# CC3351.net
KiCad netlist of a schematic drawn in Altium Designer
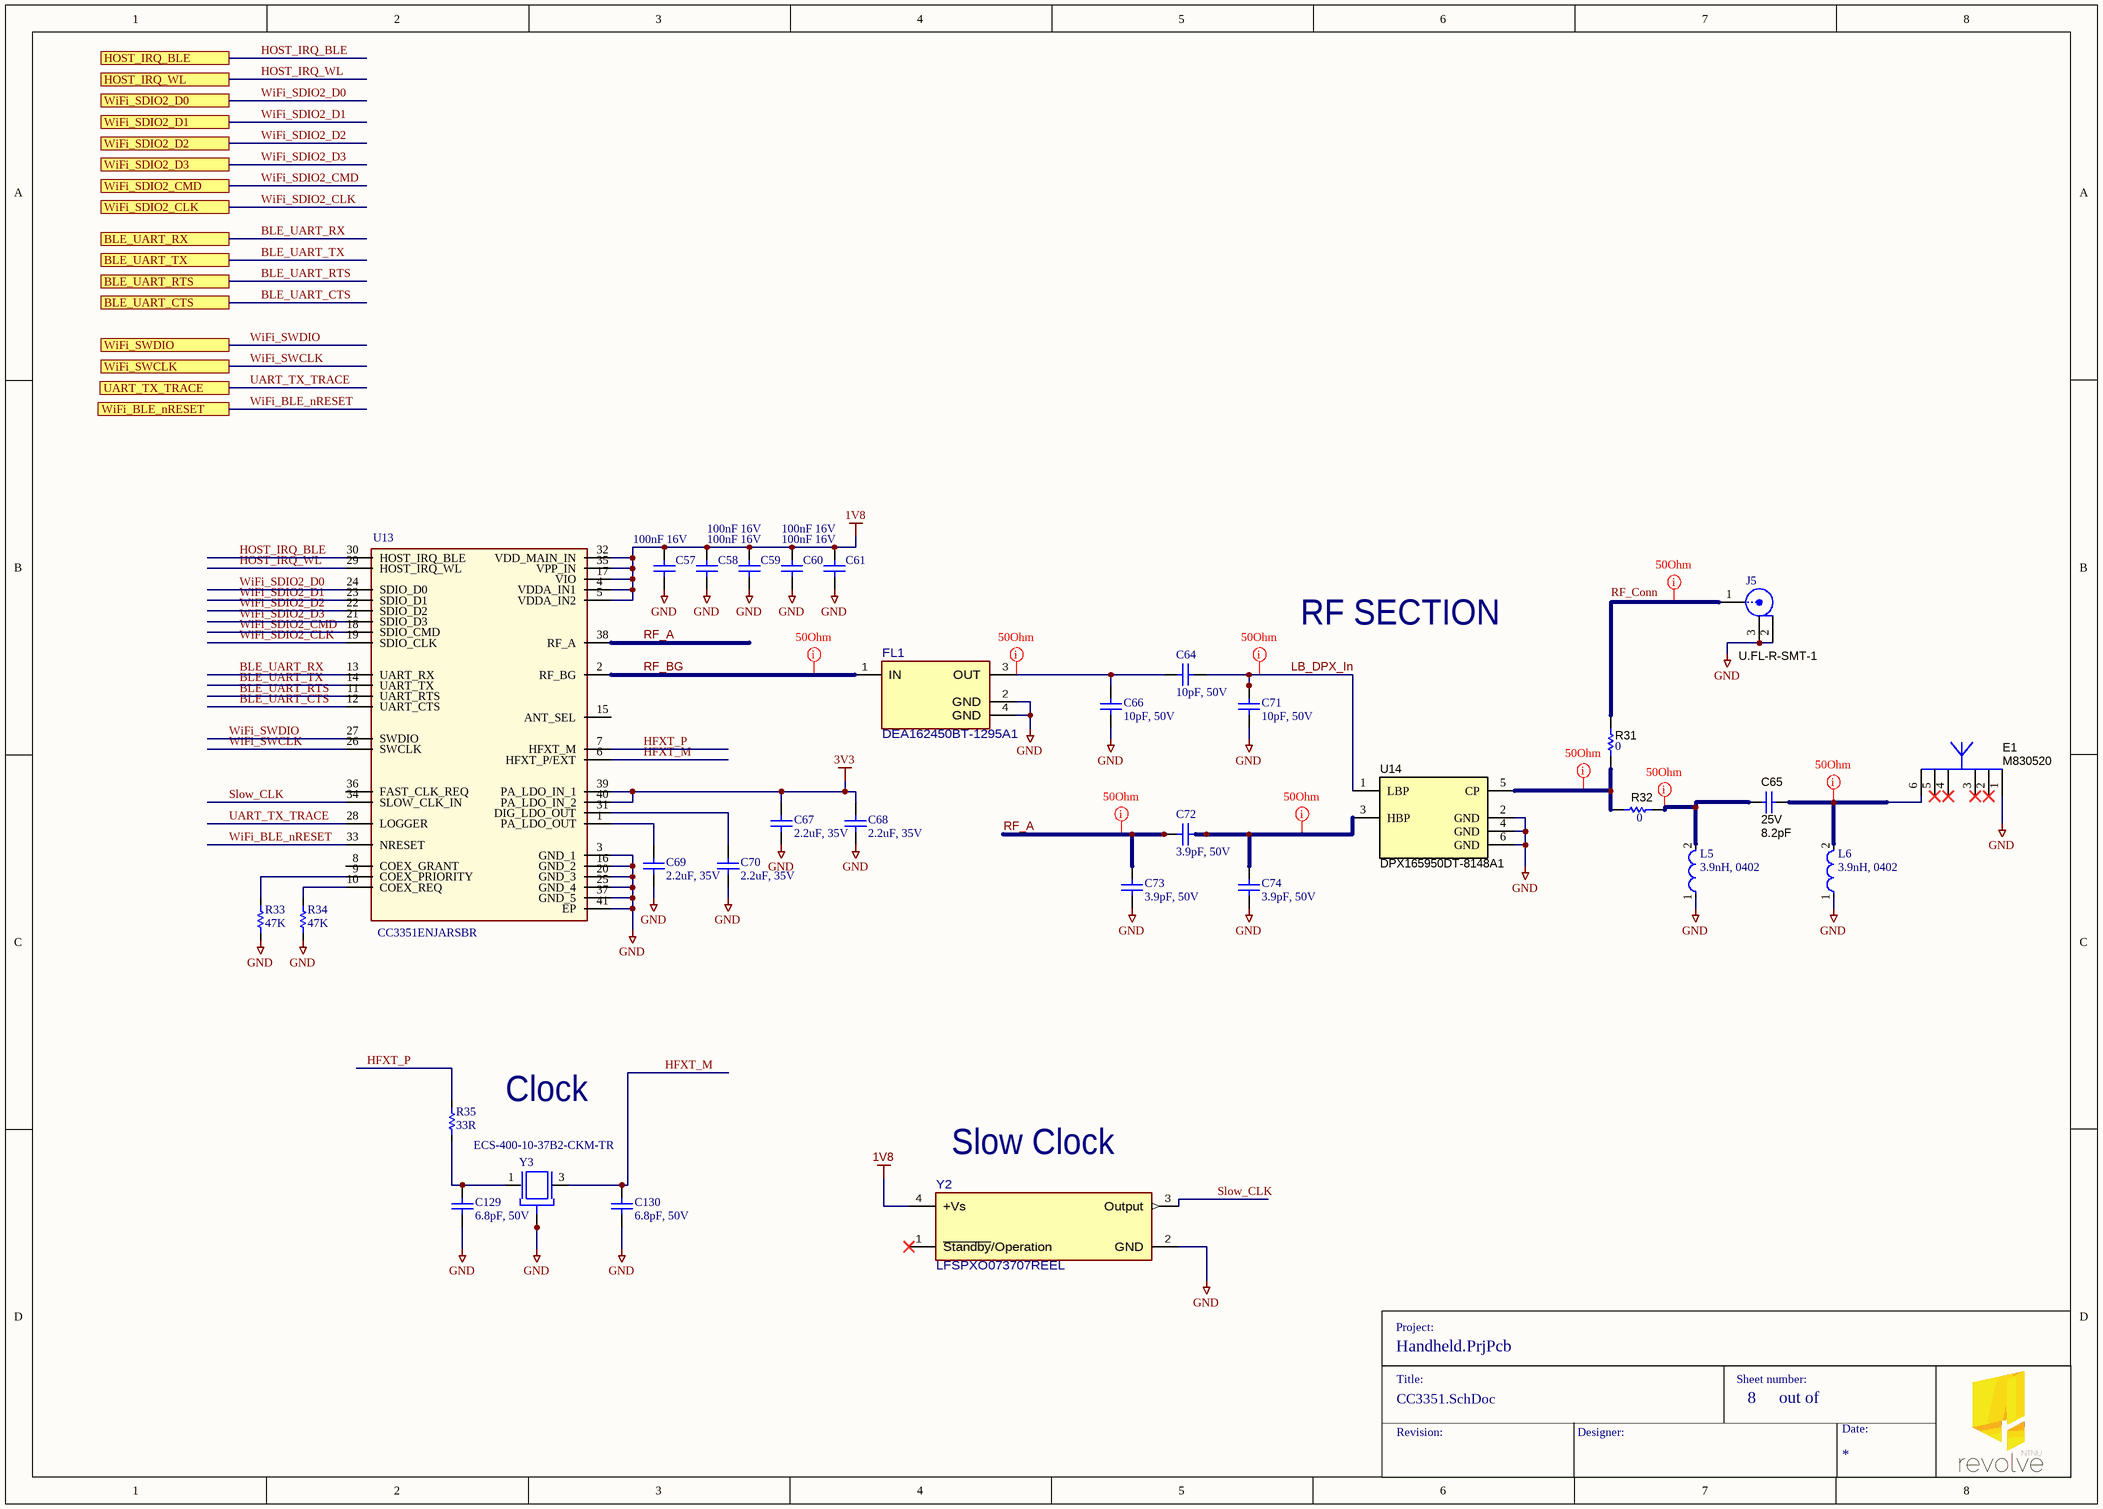
[diagram p0: CC3351.SchDoc]

(export (version "E")
  (design (tool "Eeschema 10.0.6"))
  (components
    (comp (ref "C57") (value "100nF 16V") (footprint "0402") (libsource (lib "Revolve NTNU") (part "CAP")))
    (comp (ref "C58") (value "100nF 16V") (footprint "0402") (libsource (lib "Revolve NTNU") (part "CAP")))
    (comp (ref "C59") (value "100nF 16V") (footprint "0402") (libsource (lib "Revolve NTNU") (part "CAP")))
    (comp (ref "C60") (value "100nF 16V") (footprint "0402") (libsource (lib "Revolve NTNU") (part "CAP")))
    (comp (ref "C61") (value "100nF 16V") (footprint "0402") (libsource (lib "Revolve NTNU") (part "CAP")))
    (comp (ref "C64")
      (value "10pF, 50V")
      (footprint "0402 resistor")
      (description "10pF, 50V, 10%, 0402")
      (libsource (lib "Revolve NTNU") (part "CAP"))
    )
    (comp (ref "C65")
      (value "GJM0335C1E100JB01D")
      (footprint "0201")
      (description "CAP, CERM, 8.2 pF, 25 V,+/- 1.2%, C0G/NP0, 0201")
      (fields
        (field (name "MANUFACTURER") "MuRata")
        (field (name "PARTNUMBER") "GRM0335C1E8R2BA01D")
        (field (name "VDC_V") "25V")
        (field (name "VALUEDISPLAYED") "8.2pF")
        (field (name "PUBLISHER") "Texas Instruments")
      )
      (libsource (lib "MCU127_M2-CC3351_RevA") (part "Capacitor"))
    )
    (comp (ref "C66")
      (value "10pF, 50V")
      (footprint "0402 resistor")
      (description "10pF, 50V, 10%, 0402")
      (libsource (lib "Revolve NTNU") (part "CAP"))
    )
    (comp (ref "C67")
      (value "2.2uF, 35V")
      (footprint "0402 resistor")
      (description "2.2uF, 35V, 10%, 0402")
      (libsource (lib "Revolve NTNU") (part "CAP"))
    )
    (comp (ref "C68")
      (value "2.2uF, 35V")
      (footprint "0402 resistor")
      (description "2.2uF, 35V, 10%, 0402")
      (libsource (lib "Revolve NTNU") (part "CAP"))
    )
    (comp (ref "C69")
      (value "2.2uF, 35V")
      (footprint "0402 resistor")
      (description "2.2uF, 35V, 10%, 0402")
      (libsource (lib "Revolve NTNU") (part "CAP"))
    )
    (comp (ref "C70")
      (value "2.2uF, 35V")
      (footprint "0402 resistor")
      (description "2.2uF, 35V, 10%, 0402")
      (libsource (lib "Revolve NTNU") (part "CAP"))
    )
    (comp (ref "C71")
      (value "10pF, 50V")
      (footprint "0402 resistor")
      (description "10pF, 50V, 10%, 0402")
      (libsource (lib "Revolve NTNU") (part "CAP"))
    )
    (comp (ref "C72")
      (value "3.9pF, 50V")
      (footprint "0402 resistor")
      (description "3.9pF, 50V, 10%, 0402")
      (libsource (lib "Revolve NTNU") (part "CAP"))
    )
    (comp (ref "C73")
      (value "3.9pF, 50V")
      (footprint "0402 resistor")
      (description "3.9pF, 50V, 10%, 0402")
      (libsource (lib "Revolve NTNU") (part "CAP"))
    )
    (comp (ref "C74")
      (value "3.9pF, 50V")
      (footprint "0402 resistor")
      (description "3.9pF, 50V, 10%, 0402")
      (libsource (lib "Revolve NTNU") (part "CAP"))
    )
    (comp (ref "C129")
      (value "6.8pF, 50V")
      (footprint "0402 resistor")
      (description "6.8pF, 50V, 10%, 0402")
      (libsource (lib "Revolve NTNU") (part "CAP"))
    )
    (comp (ref "C130")
      (value "6.8pF, 50V")
      (footprint "0402 resistor")
      (description "6.8pF, 50V, 10%, 0402")
      (libsource (lib "Revolve NTNU") (part "CAP"))
    )
    (comp (ref "E1")
      (value "M830520")
      (footprint "Ethertronics_M830520")
      (description "WLAN ANTENNA 802.11, SMD")
      (fields
        (field (name "MANUFACTURER") "Ethertronics")
        (field (name "ALTERNATE PARTNUMBER") "----")
        (field (name "PUBLISHER") "Texas Instruments")
      )
      (libsource (lib "MCU127_M2-CC3351_RevA") (part "CMP-0001857-1"))
    )
    (comp (ref "FL1")
      (value "DEA162450BT-1295A1")
      (footprint "FP-DEA162450BT-1295A1_SMT_FILTER_1MM60_0MM80-MFG")
      (fields
        (field (name "MOUSER PART NUMBER") "810-DEA162450BT1295A")
        (field (name "MANUFACTURER") "TDK")
        (field (name "DIGIKEY PART NUMBER") "445-175610-1-ND")
      )
      (libsource (lib "MCU127_M2-CC3351_RevA") (part "SYM-DEA162450BT-1295A1"))
    )
    (comp (ref "J5")
      (value "U.FL-R-SMT-1")
      (footprint "CONN_UFL-R-SMT-1")
      (description "Receptacle, Ultra Miniature Coaxial, Male Pin, 50 ohm, SMT")
      (fields
        (field (name "MANUFACTURER") "Hirose Electric Co. Ltd.")
        (field (name "PARTNUMBER") "U.FL-R-SMT-1(01)")
        (field (name "PUBLISHER") "Texas Instruments")
      )
      (libsource (lib "MCU127_M2-CC3351_RevA") (part "SMA_Contact1_GND23"))
    )
    (comp (ref "L5")
      (value "3.9nH, 0402")
      (footprint "INDC1005X55N")
      (description "3.9 nH Unshielded Multilayer Inductor 750 mA 140mOhm Max 0402 (1005 Metric)")
      (fields (field (name "TOLERANCE") "30%"))
      (libsource (lib "Handheld") (part "Inductor SMD 3.9nH"))
    )
    (comp (ref "L6")
      (value "3.9nH, 0402")
      (footprint "INDC1005X55N")
      (description "3.9 nH Unshielded Multilayer Inductor 750 mA 140mOhm Max 0402 (1005 Metric)")
      (fields (field (name "TOLERANCE") "30%"))
      (libsource (lib "Handheld") (part "Inductor SMD 3.9nH"))
    )
    (comp (ref "R31")
      (value "CRCW02010000Z0ED")
      (footprint "0201")
      (description "RES, 0, 5%, 0.05 W, 0201")
      (fields (field (name "MANUFACTURER") "Vishay-Dale") (field (name "VALUEDISPLAYED") "0"))
      (libsource (lib "MCU127_M2-CC3351_RevA") (part "Resistor"))
    )
    (comp (ref "R32")
      (value "CRCW02010000Z0ED")
      (footprint "0201")
      (description "RES, 0, 5%, 0.05 W, 0201")
      (fields (field (name "MANUFACTURER") "Vishay-Dale") (field (name "VALUEDISPLAYED") "0"))
      (libsource (lib "MCU127_M2-CC3351_RevA") (part "Resistor"))
    )
    (comp (ref "R33")
      (value "47K")
      (footprint "0603 Resistor")
      (description "47K, 1%, 1/10W, 0603")
      (libsource (lib "Revolve NTNU") (part "Resistor"))
    )
    (comp (ref "R34")
      (value "47K")
      (footprint "0603 Resistor")
      (description "47K, 1%, 1/10W, 0603")
      (libsource (lib "Revolve NTNU") (part "Resistor"))
    )
    (comp (ref "R35")
      (value "33R")
      (footprint "0603 Resistor")
      (description "33R, 1%, 1/10W, 0603")
      (fields (field (name "TOLERANCE") "1%") (field (name "MANUFACTURER") "Panasonic"))
      (libsource (lib "Revolve NTNU") (part "Resistor"))
    )
    (comp (ref "U13")
      (value "CC3351ENJARSBR")
      (footprint "RSB0040B-MFG")
      (fields (field (name "MOUSER PART NUMBER") "595-CC3351ENJARSBR"))
      (libsource (lib "Handheld") (part "CC3351ENJARSBR"))
    )
    (comp (ref "U14")
      (value "CMP-0002040-1")
      (footprint "TDK_DPX165950DT-8148A1")
      (description "Multilayer Diplexer for 2.4GHz W-LAN & Bluetooth / 5GHz W-LAN")
      (fields
        (field (name "PARTNUMBER") "DPX165950DT-8148A1")
        (field (name "MANUFACTURER") "TDK")
        (field (name "ALTERNATE PARTNUMBER") "----")
        (field (name "PUBLISHER") "Texas Instruments")
      )
      (libsource (lib "MCU127_M2-CC3351_RevA") (part "CMP-0002040-1"))
    )
    (comp (ref "Y2")
      (value "LFSPXO073707REEL")
      (footprint "FP-LFSPXO073707REEL_SMT4_2MM0_1MM6-MFG")
      (description "32.768 kHz XO (Standard) CMOS Oscillator 1.8V Enable/Disable 4-SMD, No Lead")
      (fields
        (field (name "MANUFACTURER") "IQD Frequency Products")
        (field (name "DIGIKEY PART NUMBER") "1923-1619-1-ND")
      )
      (libsource (lib "MCU127_M2-CC3351_RevA") (part "SYM-LFSPXO073707REEL"))
    )
    (comp (ref "Y3")
      (value "ECS-400-10-37B2-CKM-TR")
      (footprint "XTAL_ECS-400-10-37B2-CKM-TR")
      (description "Crystal 40MHz ±10ppm (Tol) ±10ppm (Stability) 10pF FUND 40Ohm 4-Pin Mini-CSMD T/R")
      (fields (field (name "MF") "ECS Inc."))
      (libsource (lib "Handheld") (part "ECS-400-10-37B2-CKM-TR"))
    )
  )
  (nets
    (net (code "1") (name "/BLE_UART_CTS") (class "Default")
      (node (ref "U13") (pin "12") (pinfunction "UART_CTS_12") (pintype "passive"))
    )
    (net (code "2") (name "/BLE_UART_RTS") (class "Default")
      (node (ref "U13") (pin "11") (pinfunction "UART_RTS_11") (pintype "passive"))
    )
    (net (code "3") (name "/BLE_UART_RX") (class "Default")
      (node (ref "U13") (pin "13") (pinfunction "UART_RX_13") (pintype "passive"))
    )
    (net (code "4") (name "/BLE_UART_TX") (class "Default")
      (node (ref "U13") (pin "14") (pinfunction "UART_TX_14") (pintype "passive"))
    )
    (net (code "5") (name "/HFXT_M") (class "Default")
      (node (ref "C130") (pin "2") (pinfunction "2_2") (pintype "passive"))
      (node (ref "U13") (pin "6") (pinfunction "HFXT_P/EXT_6") (pintype "passive"))
      (node (ref "Y3") (pin "3") (pinfunction "OUT/IN_3") (pintype "passive"))
    )
    (net (code "6") (name "/HFXT_P") (class "Default")
      (node (ref "R35") (pin "2") (pinfunction "2_2") (pintype "passive"))
      (node (ref "U13") (pin "7") (pinfunction "HFXT_M_7") (pintype "passive"))
    )
    (net (code "7") (name "/HOST_IRQ_BLE") (class "Default")
      (node (ref "U13") (pin "30") (pinfunction "HOST_IRQ_BLE_30") (pintype "passive"))
    )
    (net (code "8") (name "/HOST_IRQ_WL") (class "Default")
      (node (ref "U13") (pin "29") (pinfunction "HOST_IRQ_WL_29") (pintype "passive"))
    )
    (net (code "9") (name "/LB_DPX_In") (class "Default")
      (node (ref "C64") (pin "2") (pinfunction "2_2") (pintype "passive"))
      (node (ref "C71") (pin "2") (pinfunction "2_2") (pintype "passive"))
      (node (ref "U14") (pin "1") (pinfunction "LBP_1") (pintype "passive"))
    )
    (net (code "10") (name "/RF_A") (class "Default")
      (node (ref "C72") (pin "2") (pinfunction "2_2") (pintype "passive"))
      (node (ref "C73") (pin "2") (pinfunction "2_2") (pintype "passive"))
      (node (ref "U13") (pin "38") (pinfunction "RF_A_38") (pintype "passive"))
    )
    (net (code "11") (name "/RF_BG") (class "Default")
      (node (ref "FL1") (pin "1") (pinfunction "IN_1") (pintype "passive"))
      (node (ref "U13") (pin "2") (pinfunction "RF_BG_2") (pintype "passive"))
    )
    (net (code "13") (name "/Slow_CLK") (class "Default")
      (node (ref "U13") (pin "34") (pinfunction "SLOW_CLK_IN_34") (pintype "passive"))
      (node (ref "Y2") (pin "3") (pinfunction "Output_3") (pintype "output"))
    )
    (net (code "14") (name "/UART_TX_TRACE") (class "Default")
      (node (ref "U13") (pin "28") (pinfunction "LOGGER_28") (pintype "passive"))
    )
    (net (code "15") (name "/WiFi_BLE_nRESET") (class "Default")
      (node (ref "U13") (pin "33") (pinfunction "NRESET_33") (pintype "passive"))
    )
    (net (code "16") (name "/WiFi_SDIO2_CLK") (class "Default")
      (node (ref "U13") (pin "19") (pinfunction "SDIO_CLK_19") (pintype "passive"))
    )
    (net (code "17") (name "/WiFi_SDIO2_CMD") (class "Default")
      (node (ref "U13") (pin "18") (pinfunction "SDIO_CMD_18") (pintype "passive"))
    )
    (net (code "18") (name "/WiFi_SDIO2_D0") (class "Default")
      (node (ref "U13") (pin "24") (pinfunction "SDIO_D0_24") (pintype "passive"))
    )
    (net (code "19") (name "/WiFi_SDIO2_D1") (class "Default")
      (node (ref "U13") (pin "23") (pinfunction "SDIO_D1_23") (pintype "passive"))
    )
    (net (code "20") (name "/WiFi_SDIO2_D2") (class "Default")
      (node (ref "U13") (pin "22") (pinfunction "SDIO_D2_22") (pintype "passive"))
    )
    (net (code "21") (name "/WiFi_SDIO2_D3") (class "Default")
      (node (ref "U13") (pin "21") (pinfunction "SDIO_D3_21") (pintype "passive"))
    )
    (net (code "22") (name "/WiFi_SWCLK") (class "Default")
      (node (ref "U13") (pin "26") (pinfunction "SWCLK_26") (pintype "passive"))
    )
    (net (code "23") (name "/WiFi_SWDIO") (class "Default")
      (node (ref "U13") (pin "27") (pinfunction "SWDIO_27") (pintype "passive"))
    )
    (net (code "24") (name "1V8") (class "Default")
      (node (ref "C57") (pin "2") (pinfunction "2_2") (pintype "passive"))
      (node (ref "C58") (pin "2") (pinfunction "2_2") (pintype "passive"))
      (node (ref "C59") (pin "2") (pinfunction "2_2") (pintype "passive"))
      (node (ref "C60") (pin "2") (pinfunction "2_2") (pintype "passive"))
      (node (ref "C61") (pin "2") (pinfunction "2_2") (pintype "passive"))
      (node (ref "U13") (pin "17") (pinfunction "VIO_17") (pintype "passive"))
      (node (ref "U13") (pin "32") (pinfunction "VDD_MAIN_IN_32") (pintype "passive"))
      (node (ref "U13") (pin "35") (pinfunction "VPP_IN_35") (pintype "passive"))
      (node (ref "U13") (pin "4") (pinfunction "VDDA_IN1_4") (pintype "passive"))
      (node (ref "U13") (pin "5") (pinfunction "VDDA_IN2_5") (pintype "passive"))
      (node (ref "Y2") (pin "4") (pinfunction "+Vs_4") (pintype "power_in"))
    )
    (net (code "25") (name "3V3") (class "Default")
      (node (ref "C67") (pin "2") (pinfunction "2_2") (pintype "passive"))
      (node (ref "C68") (pin "2") (pinfunction "2_2") (pintype "passive"))
      (node (ref "U13") (pin "39") (pinfunction "PA_LDO_IN_1_39") (pintype "passive"))
      (node (ref "U13") (pin "40") (pinfunction "PA_LDO_IN_2_40") (pintype "passive"))
    )
    (net (code "26") (name "GND") (class "Default")
      (node (ref "C129") (pin "1") (pinfunction "1_1") (pintype "passive"))
      (node (ref "C130") (pin "1") (pinfunction "1_1") (pintype "passive"))
      (node (ref "C57") (pin "1") (pinfunction "1_1") (pintype "passive"))
      (node (ref "C58") (pin "1") (pinfunction "1_1") (pintype "passive"))
      (node (ref "C59") (pin "1") (pinfunction "1_1") (pintype "passive"))
      (node (ref "C60") (pin "1") (pinfunction "1_1") (pintype "passive"))
      (node (ref "C61") (pin "1") (pinfunction "1_1") (pintype "passive"))
      (node (ref "C66") (pin "1") (pinfunction "1_1") (pintype "passive"))
      (node (ref "C67") (pin "1") (pinfunction "1_1") (pintype "passive"))
      (node (ref "C68") (pin "1") (pinfunction "1_1") (pintype "passive"))
      (node (ref "C69") (pin "1") (pinfunction "1_1") (pintype "passive"))
      (node (ref "C70") (pin "1") (pinfunction "1_1") (pintype "passive"))
      (node (ref "C71") (pin "1") (pinfunction "1_1") (pintype "passive"))
      (node (ref "C73") (pin "1") (pinfunction "1_1") (pintype "passive"))
      (node (ref "C74") (pin "1") (pinfunction "1_1") (pintype "passive"))
      (node (ref "E1") (pin "1") (pinfunction "Feed_1") (pintype "passive"))
      (node (ref "FL1") (pin "2") (pinfunction "GND_2") (pintype "power_in"))
      (node (ref "FL1") (pin "4") (pinfunction "GND_4") (pintype "power_in"))
      (node (ref "J5") (pin "2") (pinfunction "2_2") (pintype "passive"))
      (node (ref "J5") (pin "3") (pinfunction "3_3") (pintype "passive"))
      (node (ref "L5") (pin "1") (pinfunction "1_1") (pintype "passive"))
      (node (ref "L6") (pin "1") (pinfunction "1_1") (pintype "passive"))
      (node (ref "R33") (pin "2") (pinfunction "2_2") (pintype "passive"))
      (node (ref "R34") (pin "2") (pinfunction "2_2") (pintype "passive"))
      (node (ref "U13") (pin "16") (pinfunction "GND_2_16") (pintype "passive"))
      (node (ref "U13") (pin "20") (pinfunction "GND_3_20") (pintype "passive"))
      (node (ref "U13") (pin "25") (pinfunction "GND_4_25") (pintype "passive"))
      (node (ref "U13") (pin "3") (pinfunction "GND_1_3") (pintype "passive"))
      (node (ref "U13") (pin "37") (pinfunction "GND_5_37") (pintype "passive"))
      (node (ref "U13") (pin "41") (pinfunction "EP_41") (pintype "passive"))
      (node (ref "U14") (pin "2") (pinfunction "GND_2") (pintype "power_in"))
      (node (ref "U14") (pin "4") (pinfunction "GND_4") (pintype "power_in"))
      (node (ref "U14") (pin "6") (pinfunction "GND_6") (pintype "power_in"))
      (node (ref "Y2") (pin "2") (pinfunction "GND_2") (pintype "power_in"))
      (node (ref "Y3") (pin "2") (pinfunction "GND_2") (pintype "power_in"))
      (node (ref "Y3") (pin "4") (pinfunction "GND_4") (pintype "power_in"))
    )
    (net (code "27") (name "Net-(C65-Pad1)") (class "Default")
      (node (ref "C65") (pin "1") (pinfunction "1_1") (pintype "passive"))
      (node (ref "E1") (pin "6") (pinfunction "6_6") (pintype "passive"))
      (node (ref "L6") (pin "2") (pinfunction "2_2") (pintype "passive"))
    )
    (net (code "28") (name "Net-(C65-Pad2)") (class "Default")
      (node (ref "C65") (pin "2") (pinfunction "2_2") (pintype "passive"))
      (node (ref "L5") (pin "2") (pinfunction "2_2") (pintype "passive"))
      (node (ref "R32") (pin "2") (pinfunction "2_2") (pintype "passive"))
    )
    (net (code "29") (name "Net-(FL1-OUT)") (class "Default")
      (node (ref "C64") (pin "1") (pinfunction "1_1") (pintype "passive"))
      (node (ref "C66") (pin "2") (pinfunction "2_2") (pintype "passive"))
      (node (ref "FL1") (pin "3") (pinfunction "OUT_3") (pintype "passive"))
    )
    (net (code "30") (name "Net-(J5-Pad1)") (class "Default")
      (node (ref "J5") (pin "1") (pinfunction "1_1") (pintype "passive"))
      (node (ref "R31") (pin "2") (pinfunction "2_2") (pintype "passive"))
    )
    (net (code "31") (name "Net-(U13-COEX_PRIORITY)") (class "Default")
      (node (ref "R33") (pin "1") (pinfunction "1_1") (pintype "passive"))
      (node (ref "U13") (pin "9") (pinfunction "COEX_PRIORITY_9") (pintype "passive"))
    )
    (net (code "32") (name "Net-(U13-COEX_REQ)") (class "Default")
      (node (ref "R34") (pin "1") (pinfunction "1_1") (pintype "passive"))
      (node (ref "U13") (pin "10") (pinfunction "COEX_REQ_10") (pintype "passive"))
    )
    (net (code "33") (name "Net-(U13-DIG_LDO_OUT)") (class "Default")
      (node (ref "C70") (pin "2") (pinfunction "2_2") (pintype "passive"))
      (node (ref "U13") (pin "31") (pinfunction "DIG_LDO_OUT_31") (pintype "passive"))
    )
    (net (code "34") (name "Net-(U13-PA_LDO_OUT)") (class "Default")
      (node (ref "C69") (pin "2") (pinfunction "2_2") (pintype "passive"))
      (node (ref "U13") (pin "1") (pinfunction "PA_LDO_OUT_1") (pintype "passive"))
    )
    (net (code "35") (name "Net-(U14-CP)") (class "Default")
      (node (ref "R31") (pin "1") (pinfunction "1_1") (pintype "passive"))
      (node (ref "R32") (pin "1") (pinfunction "1_1") (pintype "passive"))
      (node (ref "U14") (pin "5") (pinfunction "CP_5") (pintype "passive"))
    )
    (net (code "36") (name "Net-(U14-HBP)") (class "Default")
      (node (ref "C72") (pin "1") (pinfunction "1_1") (pintype "passive"))
      (node (ref "C74") (pin "2") (pinfunction "2_2") (pintype "passive"))
      (node (ref "U14") (pin "3") (pinfunction "HBP_3") (pintype "passive"))
    )
    (net (code "37") (name "Net-(Y3-IN{slash}OUT)") (class "Default")
      (node (ref "C129") (pin "2") (pinfunction "2_2") (pintype "passive"))
      (node (ref "R35") (pin "1") (pinfunction "1_1") (pintype "passive"))
      (node (ref "Y3") (pin "1") (pinfunction "IN/OUT_1") (pintype "passive"))
    )
    (net (code "38") (name "unconnected-(E1-Feed-Pad4)") (class "Default")
      (node (ref "E1") (pin "4") (pinfunction "Feed_4") (pintype "passive+no_connect"))
    )
    (net (code "39") (name "unconnected-(E1-GND-Pad2)") (class "Default")
      (node (ref "E1") (pin "2") (pinfunction "GND_2") (pintype "power_in+no_connect"))
    )
    (net (code "40") (name "unconnected-(E1-GND-Pad3)") (class "Default")
      (node (ref "E1") (pin "3") (pinfunction "GND_3") (pintype "power_in+no_connect"))
    )
    (net (code "41") (name "unconnected-(E1-Pad5)") (class "Default")
      (node (ref "E1") (pin "5") (pinfunction "5_5") (pintype "passive+no_connect"))
    )
    (net (code "42") (name "unconnected-(U13-ANT_SEL-Pad15)") (class "Default")
      (node (ref "U13") (pin "15") (pinfunction "ANT_SEL_15") (pintype "passive"))
    )
    (net (code "43") (name "unconnected-(U13-COEX_GRANT-Pad8)") (class "Default")
      (node (ref "U13") (pin "8") (pinfunction "COEX_GRANT_8") (pintype "passive"))
    )
    (net (code "44") (name "unconnected-(U13-FAST_CLK_REQ-Pad36)") (class "Default")
      (node (ref "U13") (pin "36") (pinfunction "FAST_CLK_REQ_36") (pintype "passive"))
    )
    (net (code "45") (name "unconnected-(Y2-~{Standby}{slash}Operation-Pad1)") (class "Default")
      (node (ref "Y2") (pin "1") (pinfunction "~{Standby}/Operation_1") (pintype "passive+no_connect"))
    )
  )
)
